# BlinkyBoard-testcard.net
KiCad netlist of a schematic drawn in EAGLE
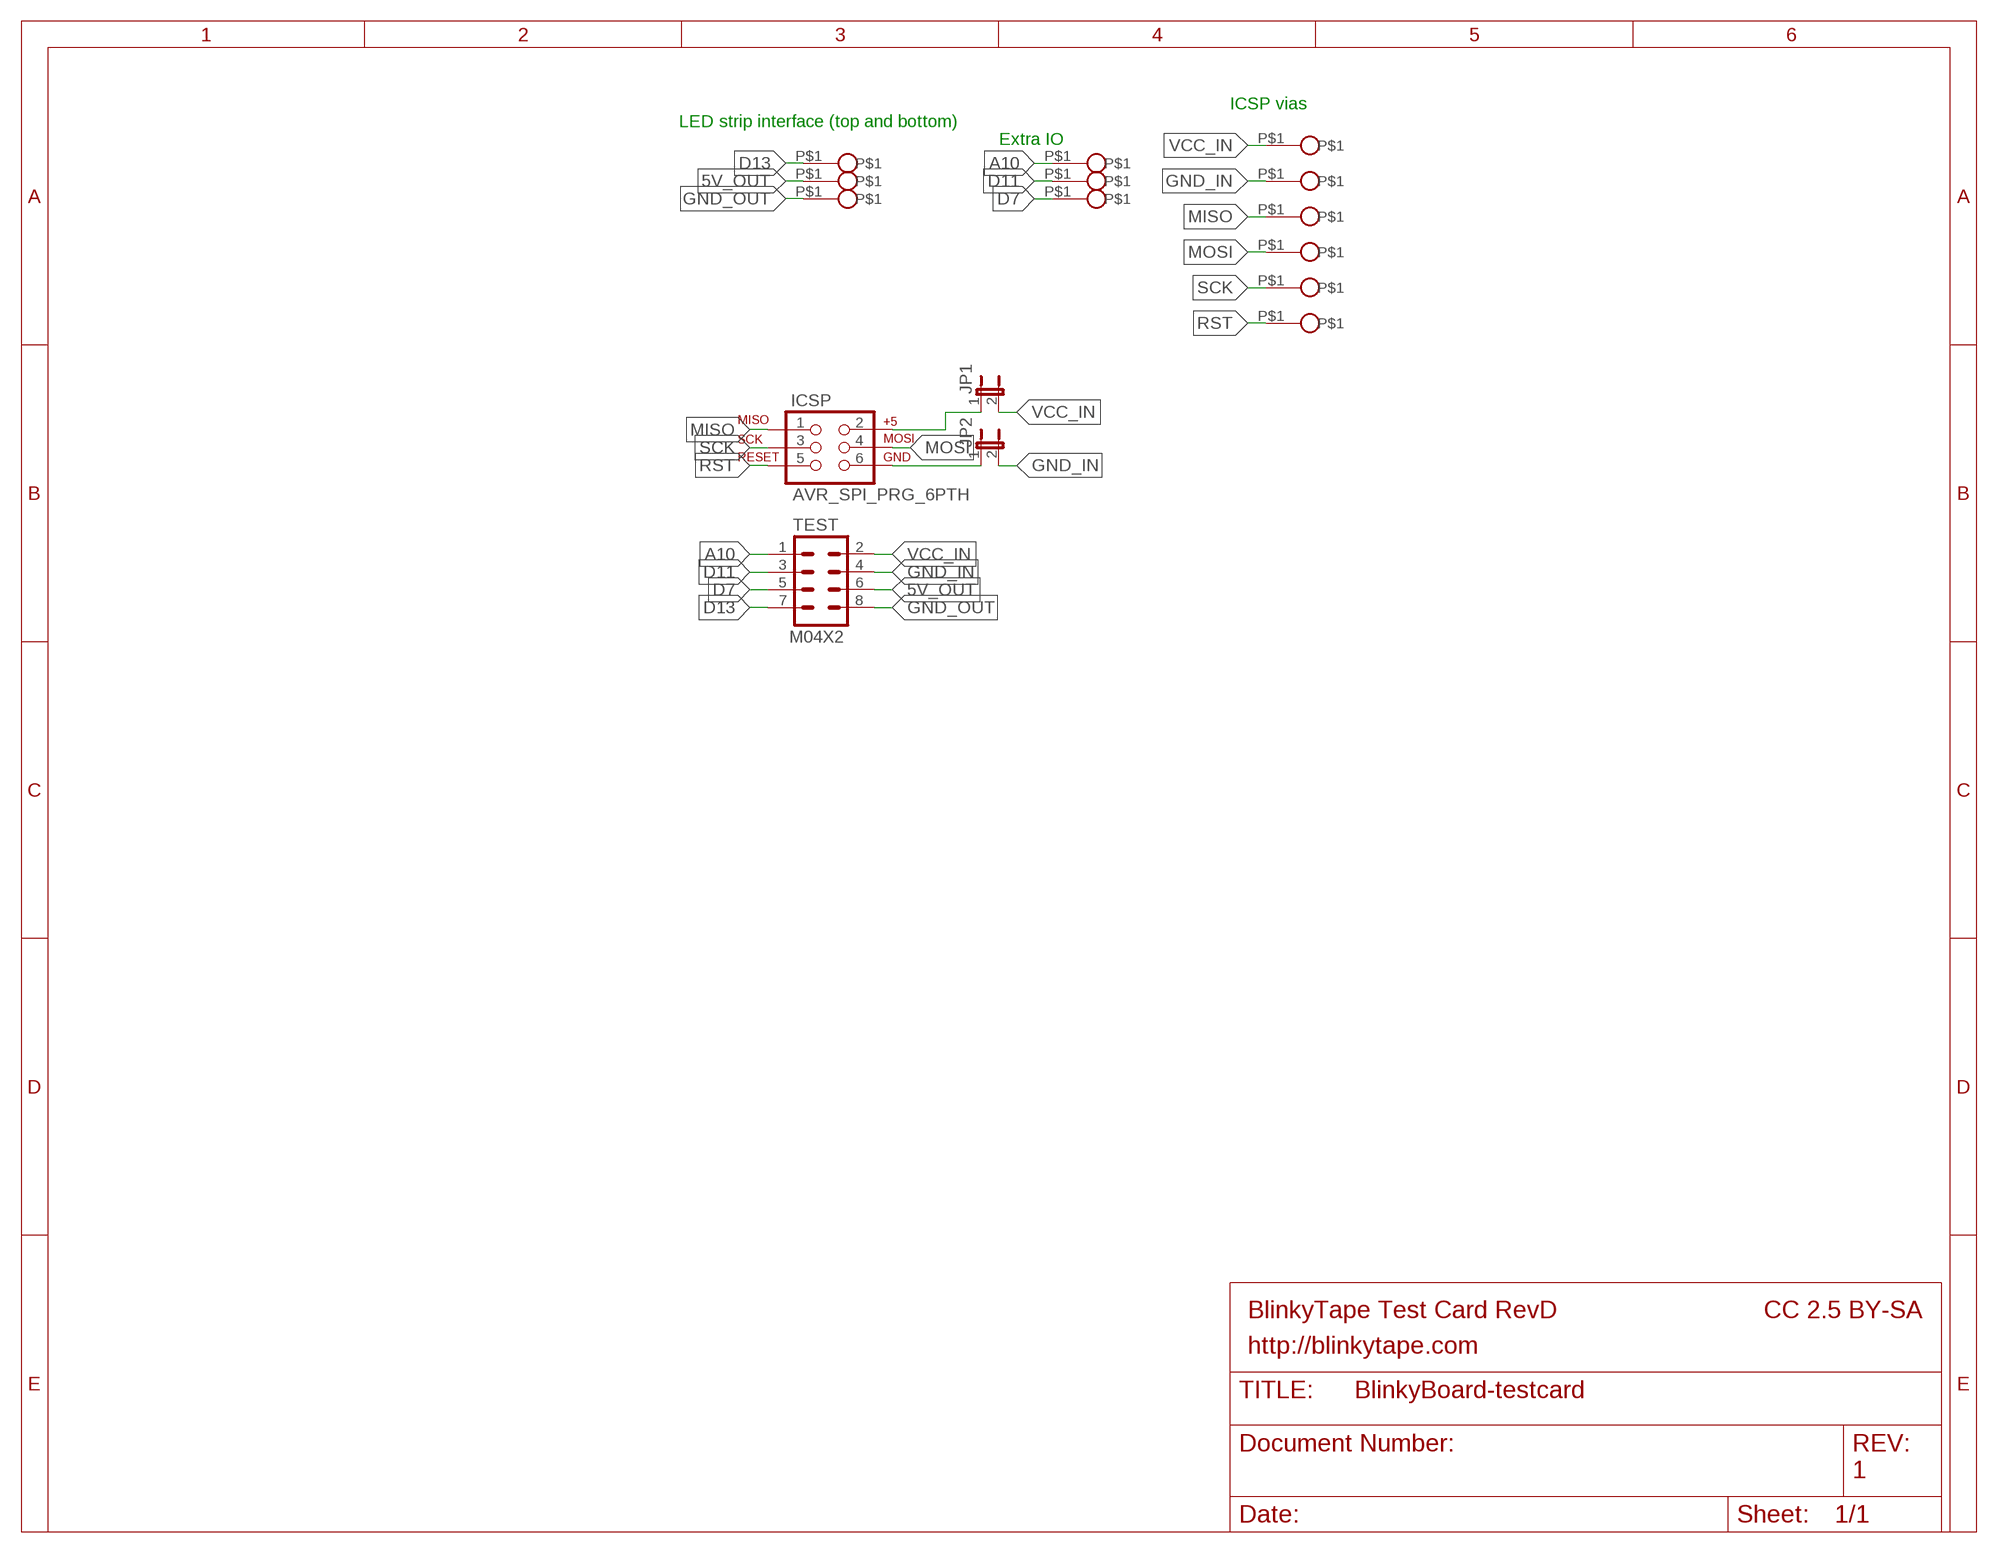
[diagram p0: schematic, sheet 1]

(export (version "E")
  (design (tool "Eeschema 10.0.6"))
  (components
    (comp (ref "ICSP")
      (value "AVR_SPI_PRG_6PTH")
      (footprint "eagle-import:2X3")
      (libsource (lib "eagle-import") (part "AVR_SPI_PRG_6PTH"))
    )
    (comp (ref "JP1")
      (value "JUMPER-2PTH")
      (footprint "eagle-import:1X02")
      (libsource (lib "eagle-import") (part "JUMPER-2PTH"))
    )
    (comp (ref "JP2")
      (value "JUMPER-2PTH")
      (footprint "eagle-import:1X02")
      (libsource (lib "eagle-import") (part "JUMPER-2PTH"))
    )
    (comp (ref "TEST")
      (value "M04X2")
      (footprint "eagle-import:2X4")
      (libsource (lib "eagle-import") (part "M04X2"))
    )
    (comp (ref "U$9")
      (value "POGO_PIN")
      (footprint "eagle-import:POGO_PIN_1MM")
      (libsource (lib "eagle-import") (part "POGO_PIN"))
    )
    (comp (ref "U$16")
      (value "POGO_PIN")
      (footprint "eagle-import:POGO_PIN_1MM")
      (libsource (lib "eagle-import") (part "POGO_PIN"))
    )
    (comp (ref "U$17")
      (value "POGO_PINOBLONG")
      (footprint "eagle-import:POGO_PIN_1MM_OBLONG")
      (libsource (lib "eagle-import") (part "POGO_PINOBLONG"))
    )
    (comp (ref "U$18")
      (value "POGO_PINOBLONG")
      (footprint "eagle-import:POGO_PIN_1MM_OBLONG")
      (libsource (lib "eagle-import") (part "POGO_PINOBLONG"))
    )
    (comp (ref "U$19")
      (value "POGO_PINOBLONG")
      (footprint "eagle-import:POGO_PIN_1MM_OBLONG")
      (libsource (lib "eagle-import") (part "POGO_PINOBLONG"))
    )
    (comp (ref "U$20")
      (value "POGO_PINOBLONG")
      (footprint "eagle-import:POGO_PIN_1MM_OBLONG")
      (libsource (lib "eagle-import") (part "POGO_PINOBLONG"))
    )
    (comp (ref "U$22")
      (value "POGO_PIN")
      (footprint "eagle-import:POGO_PIN_1MM")
      (libsource (lib "eagle-import") (part "POGO_PIN"))
    )
    (comp (ref "U$23")
      (value "POGO_PIN")
      (footprint "eagle-import:POGO_PIN_1MM")
      (libsource (lib "eagle-import") (part "POGO_PIN"))
    )
    (comp (ref "U$24")
      (value "POGO_PIN")
      (footprint "eagle-import:POGO_PIN_1MM")
      (libsource (lib "eagle-import") (part "POGO_PIN"))
    )
    (comp (ref "U$26")
      (value "POGO_PIN")
      (footprint "eagle-import:POGO_PIN_1MM")
      (libsource (lib "eagle-import") (part "POGO_PIN"))
    )
    (comp (ref "U$27")
      (value "POGO_PIN")
      (footprint "eagle-import:POGO_PIN_1MM")
      (libsource (lib "eagle-import") (part "POGO_PIN"))
    )
    (comp (ref "U$28")
      (value "POGO_PIN")
      (footprint "eagle-import:POGO_PIN_1MM")
      (libsource (lib "eagle-import") (part "POGO_PIN"))
    )
  )
  (nets
    (net (code "1") (name "5V_OUT") (class "Default")
      (node (ref "TEST") (pin "6") (pinfunction "6_6") (pintype "passive"))
      (node (ref "U$27") (pin "P$1") (pinfunction "P$1_P$1") (pintype "bidirectional"))
    )
    (net (code "2") (name "A10") (class "Default")
      (node (ref "TEST") (pin "1") (pinfunction "1_1") (pintype "passive"))
      (node (ref "U$22") (pin "P$1") (pinfunction "P$1_P$1") (pintype "bidirectional"))
    )
    (net (code "3") (name "D7") (class "Default")
      (node (ref "TEST") (pin "5") (pinfunction "5_5") (pintype "passive"))
      (node (ref "U$24") (pin "P$1") (pinfunction "P$1_P$1") (pintype "bidirectional"))
    )
    (net (code "4") (name "D11") (class "Default")
      (node (ref "TEST") (pin "3") (pinfunction "3_3") (pintype "passive"))
      (node (ref "U$23") (pin "P$1") (pinfunction "P$1_P$1") (pintype "bidirectional"))
    )
    (net (code "5") (name "D13") (class "Default")
      (node (ref "TEST") (pin "7") (pinfunction "7_7") (pintype "passive"))
      (node (ref "U$26") (pin "P$1") (pinfunction "P$1_P$1") (pintype "bidirectional"))
    )
    (net (code "6") (name "GND_IN") (class "Default")
      (node (ref "JP2") (pin "2") (pinfunction "2_2") (pintype "passive"))
      (node (ref "TEST") (pin "4") (pinfunction "4_4") (pintype "passive"))
      (node (ref "U$16") (pin "P$1") (pinfunction "P$1_P$1") (pintype "bidirectional"))
    )
    (net (code "7") (name "GND_OUT") (class "Default")
      (node (ref "TEST") (pin "8") (pinfunction "8_8") (pintype "passive"))
      (node (ref "U$28") (pin "P$1") (pinfunction "P$1_P$1") (pintype "bidirectional"))
    )
    (net (code "8") (name "MISO") (class "Default")
      (node (ref "ICSP") (pin "1") (pinfunction "1_1") (pintype "passive"))
      (node (ref "U$17") (pin "P$1") (pinfunction "P$1_P$1") (pintype "bidirectional"))
    )
    (net (code "9") (name "MOSI") (class "Default")
      (node (ref "ICSP") (pin "4") (pinfunction "4_4") (pintype "passive"))
      (node (ref "U$18") (pin "P$1") (pinfunction "P$1_P$1") (pintype "bidirectional"))
    )
    (net (code "10") (name "Net-(ICSP-Pad2)") (class "Default")
      (node (ref "ICSP") (pin "2") (pinfunction "2_2") (pintype "passive"))
      (node (ref "JP1") (pin "1") (pinfunction "1_1") (pintype "passive"))
    )
    (net (code "11") (name "Net-(ICSP-Pad6)") (class "Default")
      (node (ref "ICSP") (pin "6") (pinfunction "6_6") (pintype "passive"))
      (node (ref "JP2") (pin "1") (pinfunction "1_1") (pintype "passive"))
    )
    (net (code "12") (name "RST") (class "Default")
      (node (ref "ICSP") (pin "5") (pinfunction "5_5") (pintype "passive"))
      (node (ref "U$20") (pin "P$1") (pinfunction "P$1_P$1") (pintype "bidirectional"))
    )
    (net (code "13") (name "SCK") (class "Default")
      (node (ref "ICSP") (pin "3") (pinfunction "3_3") (pintype "passive"))
      (node (ref "U$19") (pin "P$1") (pinfunction "P$1_P$1") (pintype "bidirectional"))
    )
    (net (code "14") (name "VCC_IN") (class "Default")
      (node (ref "JP1") (pin "2") (pinfunction "2_2") (pintype "passive"))
      (node (ref "TEST") (pin "2") (pinfunction "2_2") (pintype "passive"))
      (node (ref "U$9") (pin "P$1") (pinfunction "P$1_P$1") (pintype "bidirectional"))
    )
  )
)
